# WT8266.net
KiCad netlist of a schematic drawn in EAGLE
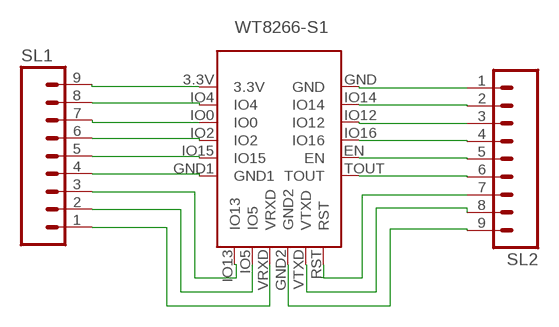
[diagram p0: schematic, sheet 1]

(export (version "E")
  (design (tool "Eeschema 10.0.6"))
  (components
    (comp (ref "SL1")
      (value "MA09")
      (footprint "eagle-import:09PA")
      (libsource (lib "eagle-import") (part "MA09"))
    )
    (comp (ref "SL2")
      (value "MA09")
      (footprint "eagle-import:09PA")
      (libsource (lib "eagle-import") (part "MA09"))
    )
    (comp (ref "U$1")
      (value "WT8266-S1")
      (footprint "eagle-import:WT8266-S1")
      (libsource (lib "eagle-import") (part "WT8266-S1"))
    )
  )
  (nets
    (net (code "1") (name "Net-(SL1-Pad1)") (class "Default")
      (node (ref "SL1") (pin "1") (pinfunction "1_1") (pintype "passive"))
      (node (ref "U$1") (pin "VRXD") (pinfunction "VRXD_VRXD") (pintype "bidirectional"))
    )
    (net (code "2") (name "Net-(SL1-Pad2)") (class "Default")
      (node (ref "SL1") (pin "2") (pinfunction "2_2") (pintype "passive"))
      (node (ref "U$1") (pin "IO5") (pinfunction "IO5_IO5") (pintype "bidirectional"))
    )
    (net (code "3") (name "Net-(SL1-Pad3)") (class "Default")
      (node (ref "SL1") (pin "3") (pinfunction "3_3") (pintype "passive"))
      (node (ref "U$1") (pin "IO13") (pinfunction "IO13_IO13") (pintype "bidirectional"))
    )
    (net (code "4") (name "Net-(SL1-Pad4)") (class "Default")
      (node (ref "SL1") (pin "4") (pinfunction "4_4") (pintype "passive"))
      (node (ref "U$1") (pin "GND1") (pinfunction "GND1_GND1") (pintype "bidirectional"))
    )
    (net (code "5") (name "Net-(SL1-Pad5)") (class "Default")
      (node (ref "SL1") (pin "5") (pinfunction "5_5") (pintype "passive"))
      (node (ref "U$1") (pin "IO15") (pinfunction "IO15_IO15") (pintype "bidirectional"))
    )
    (net (code "6") (name "Net-(SL1-Pad6)") (class "Default")
      (node (ref "SL1") (pin "6") (pinfunction "6_6") (pintype "passive"))
      (node (ref "U$1") (pin "IO2") (pinfunction "IO2_IO2") (pintype "bidirectional"))
    )
    (net (code "7") (name "Net-(SL1-Pad7)") (class "Default")
      (node (ref "SL1") (pin "7") (pinfunction "7_7") (pintype "passive"))
      (node (ref "U$1") (pin "IO0") (pinfunction "IO0_IO0") (pintype "bidirectional"))
    )
    (net (code "8") (name "Net-(SL1-Pad8)") (class "Default")
      (node (ref "SL1") (pin "8") (pinfunction "8_8") (pintype "passive"))
      (node (ref "U$1") (pin "IO4") (pinfunction "IO4_IO4") (pintype "bidirectional"))
    )
    (net (code "9") (name "Net-(SL1-Pad9)") (class "Default")
      (node (ref "SL1") (pin "9") (pinfunction "9_9") (pintype "passive"))
      (node (ref "U$1") (pin "3.3V") (pinfunction "3.3V_3.3V") (pintype "bidirectional"))
    )
    (net (code "10") (name "Net-(SL2-Pad1)") (class "Default")
      (node (ref "SL2") (pin "1") (pinfunction "1_1") (pintype "passive"))
      (node (ref "U$1") (pin "GND") (pinfunction "GND_GND") (pintype "bidirectional"))
    )
    (net (code "11") (name "Net-(SL2-Pad2)") (class "Default")
      (node (ref "SL2") (pin "2") (pinfunction "2_2") (pintype "passive"))
      (node (ref "U$1") (pin "IO14") (pinfunction "IO14_IO14") (pintype "bidirectional"))
    )
    (net (code "12") (name "Net-(SL2-Pad3)") (class "Default")
      (node (ref "SL2") (pin "3") (pinfunction "3_3") (pintype "passive"))
      (node (ref "U$1") (pin "IO12") (pinfunction "IO12_IO12") (pintype "bidirectional"))
    )
    (net (code "13") (name "Net-(SL2-Pad4)") (class "Default")
      (node (ref "SL2") (pin "4") (pinfunction "4_4") (pintype "passive"))
      (node (ref "U$1") (pin "IO16") (pinfunction "IO16_IO16") (pintype "bidirectional"))
    )
    (net (code "14") (name "Net-(SL2-Pad5)") (class "Default")
      (node (ref "SL2") (pin "5") (pinfunction "5_5") (pintype "passive"))
      (node (ref "U$1") (pin "EN") (pinfunction "EN_EN") (pintype "bidirectional"))
    )
    (net (code "15") (name "Net-(SL2-Pad6)") (class "Default")
      (node (ref "SL2") (pin "6") (pinfunction "6_6") (pintype "passive"))
      (node (ref "U$1") (pin "TOUT") (pinfunction "TOUT_TOUT") (pintype "bidirectional"))
    )
    (net (code "16") (name "Net-(SL2-Pad7)") (class "Default")
      (node (ref "SL2") (pin "7") (pinfunction "7_7") (pintype "passive"))
      (node (ref "U$1") (pin "RST") (pinfunction "RST_RST") (pintype "bidirectional"))
    )
    (net (code "17") (name "Net-(SL2-Pad8)") (class "Default")
      (node (ref "SL2") (pin "8") (pinfunction "8_8") (pintype "passive"))
      (node (ref "U$1") (pin "VTXD") (pinfunction "VTXD_VTXD") (pintype "bidirectional"))
    )
    (net (code "18") (name "Net-(SL2-Pad9)") (class "Default")
      (node (ref "SL2") (pin "9") (pinfunction "9_9") (pintype "passive"))
      (node (ref "U$1") (pin "GND2") (pinfunction "GND2_GND2") (pintype "bidirectional"))
    )
  )
)
